# ME433Schematic.net
KiCad netlist of a schematic drawn in EAGLE
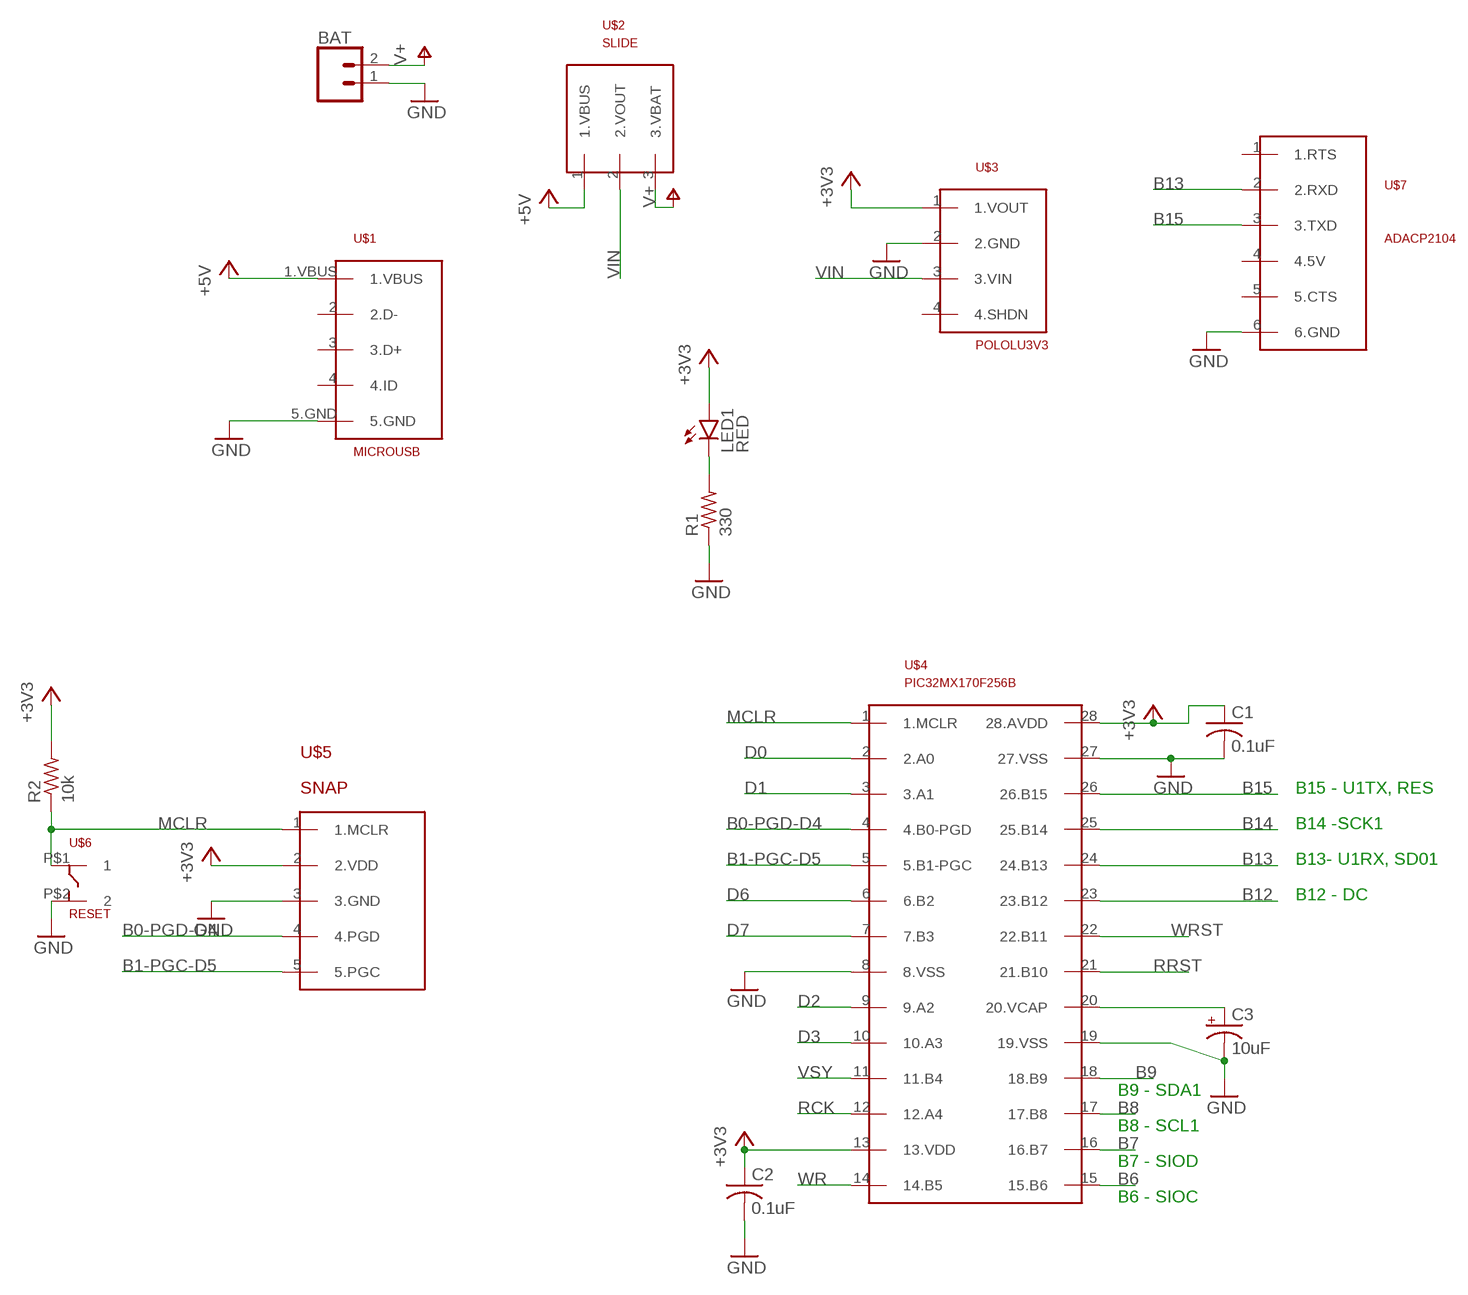
[diagram p0: schematic, sheet 1, part 1 of 2]
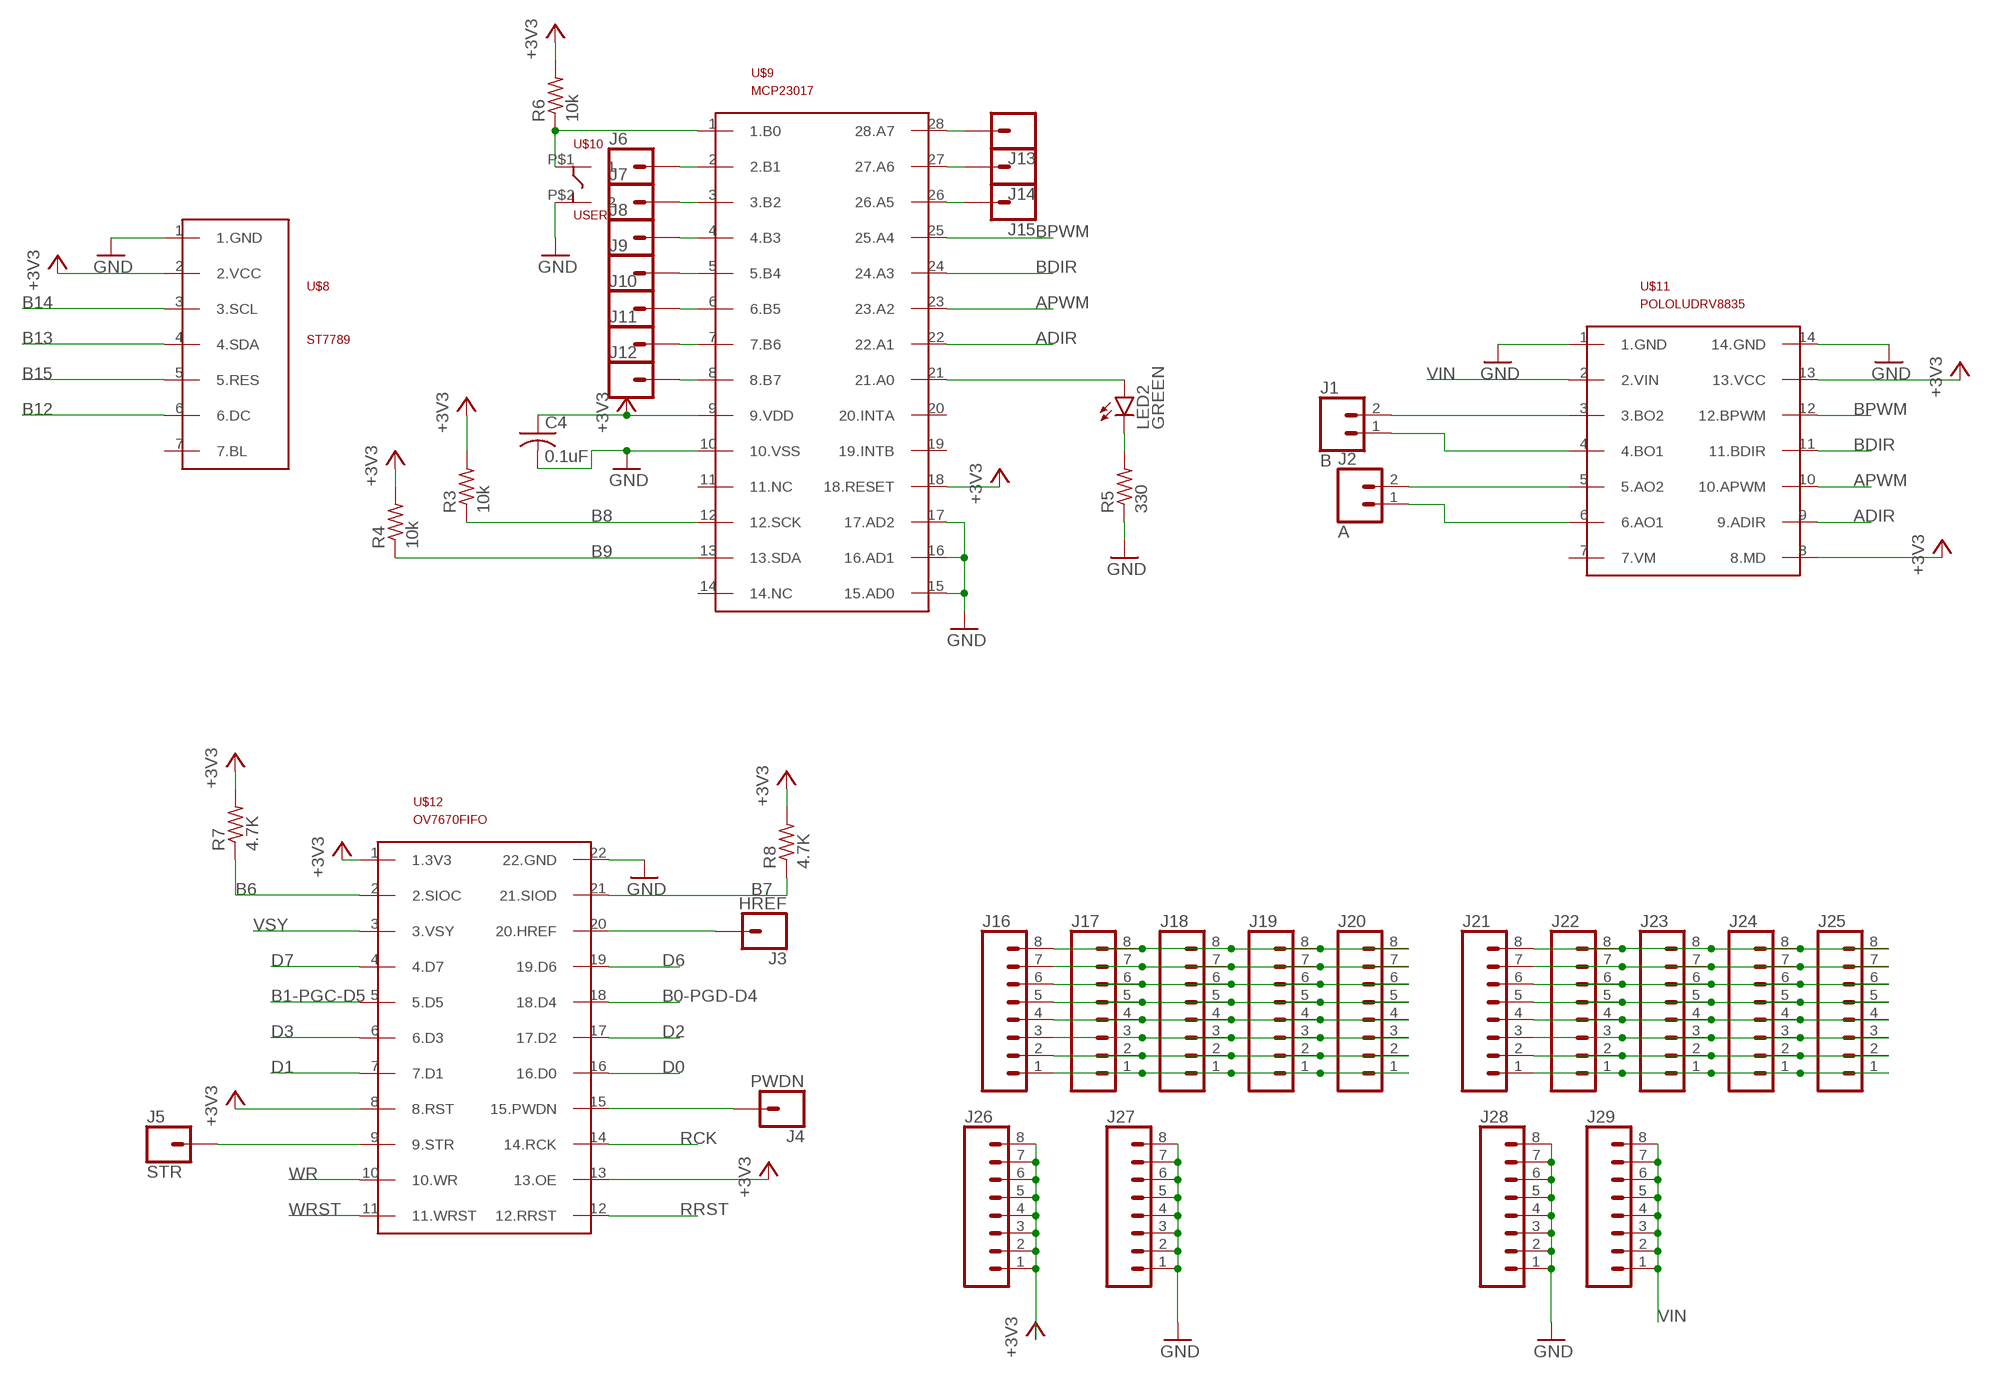
[diagram p1: schematic, sheet 1, part 2 of 2]

(export (version "E")
  (design (tool "Eeschema 10.0.6"))
  (components
    (comp (ref "BAT")
      (value "CONN_02")
      (footprint "eagle-import:1X02")
      (libsource (lib "eagle-import") (part "CONN_02"))
    )
    (comp (ref "C1")
      (value "0.1uF")
      (footprint "eagle-import:C025-030X050")
      (libsource (lib "eagle-import") (part "C-US025-030X050"))
    )
    (comp (ref "C2")
      (value "0.1uF")
      (footprint "eagle-import:C025-030X050")
      (libsource (lib "eagle-import") (part "C-US025-030X050"))
    )
    (comp (ref "C3")
      (value "10uF")
      (footprint "eagle-import:B45181B")
      (libsource (lib "eagle-import") (part "CPOL-USB45181B"))
    )
    (comp (ref "C4")
      (value "0.1uF")
      (footprint "eagle-import:C025-030X050")
      (libsource (lib "eagle-import") (part "C-US025-030X050"))
    )
    (comp (ref "J1")
      (value "B")
      (footprint "eagle-import:1X02")
      (libsource (lib "eagle-import") (part "CONN_02"))
    )
    (comp (ref "J2")
      (value "A")
      (footprint "eagle-import:1X02")
      (libsource (lib "eagle-import") (part "CONN_02"))
    )
    (comp (ref "J3")
      (value "HREF")
      (footprint "eagle-import:1X01")
      (libsource (lib "eagle-import") (part "CONN_01"))
    )
    (comp (ref "J4")
      (value "PWDN")
      (footprint "eagle-import:1X01")
      (libsource (lib "eagle-import") (part "CONN_01"))
    )
    (comp (ref "J5")
      (value "STR")
      (footprint "eagle-import:1X01")
      (libsource (lib "eagle-import") (part "CONN_01"))
    )
    (comp (ref "J6")
      (value "CONN_01")
      (footprint "eagle-import:1X01")
      (libsource (lib "eagle-import") (part "CONN_01"))
    )
    (comp (ref "J7")
      (value "CONN_01")
      (footprint "eagle-import:1X01")
      (libsource (lib "eagle-import") (part "CONN_01"))
    )
    (comp (ref "J8")
      (value "CONN_01")
      (footprint "eagle-import:1X01")
      (libsource (lib "eagle-import") (part "CONN_01"))
    )
    (comp (ref "J9")
      (value "CONN_01")
      (footprint "eagle-import:1X01")
      (libsource (lib "eagle-import") (part "CONN_01"))
    )
    (comp (ref "J10")
      (value "CONN_01")
      (footprint "eagle-import:1X01")
      (libsource (lib "eagle-import") (part "CONN_01"))
    )
    (comp (ref "J11")
      (value "CONN_01")
      (footprint "eagle-import:1X01")
      (libsource (lib "eagle-import") (part "CONN_01"))
    )
    (comp (ref "J12")
      (value "CONN_01")
      (footprint "eagle-import:1X01")
      (libsource (lib "eagle-import") (part "CONN_01"))
    )
    (comp (ref "J13")
      (value "CONN_01")
      (footprint "eagle-import:1X01")
      (libsource (lib "eagle-import") (part "CONN_01"))
    )
    (comp (ref "J14")
      (value "CONN_01")
      (footprint "eagle-import:1X01")
      (libsource (lib "eagle-import") (part "CONN_01"))
    )
    (comp (ref "J15")
      (value "CONN_01")
      (footprint "eagle-import:1X01")
      (libsource (lib "eagle-import") (part "CONN_01"))
    )
    (comp (ref "J16")
      (value "CONN_08\"")
      (footprint "eagle-import:1X08")
      (libsource (lib "eagle-import") (part "CONN_08{dblquote}"))
    )
    (comp (ref "J17")
      (value "CONN_08\"")
      (footprint "eagle-import:1X08")
      (libsource (lib "eagle-import") (part "CONN_08{dblquote}"))
    )
    (comp (ref "J18")
      (value "CONN_08\"")
      (footprint "eagle-import:1X08")
      (libsource (lib "eagle-import") (part "CONN_08{dblquote}"))
    )
    (comp (ref "J19")
      (value "CONN_08\"")
      (footprint "eagle-import:1X08")
      (libsource (lib "eagle-import") (part "CONN_08{dblquote}"))
    )
    (comp (ref "J20")
      (value "CONN_08\"")
      (footprint "eagle-import:1X08")
      (libsource (lib "eagle-import") (part "CONN_08{dblquote}"))
    )
    (comp (ref "J21")
      (value "CONN_08\"")
      (footprint "eagle-import:1X08")
      (libsource (lib "eagle-import") (part "CONN_08{dblquote}"))
    )
    (comp (ref "J22")
      (value "CONN_08\"")
      (footprint "eagle-import:1X08")
      (libsource (lib "eagle-import") (part "CONN_08{dblquote}"))
    )
    (comp (ref "J23")
      (value "CONN_08\"")
      (footprint "eagle-import:1X08")
      (libsource (lib "eagle-import") (part "CONN_08{dblquote}"))
    )
    (comp (ref "J24")
      (value "CONN_08\"")
      (footprint "eagle-import:1X08")
      (libsource (lib "eagle-import") (part "CONN_08{dblquote}"))
    )
    (comp (ref "J25")
      (value "CONN_08\"")
      (footprint "eagle-import:1X08")
      (libsource (lib "eagle-import") (part "CONN_08{dblquote}"))
    )
    (comp (ref "J26")
      (value "CONN_08\"")
      (footprint "eagle-import:1X08")
      (libsource (lib "eagle-import") (part "CONN_08{dblquote}"))
    )
    (comp (ref "J27")
      (value "CONN_08\"")
      (footprint "eagle-import:1X08")
      (libsource (lib "eagle-import") (part "CONN_08{dblquote}"))
    )
    (comp (ref "J28")
      (value "CONN_08\"")
      (footprint "eagle-import:1X08")
      (libsource (lib "eagle-import") (part "CONN_08{dblquote}"))
    )
    (comp (ref "J29")
      (value "CONN_08\"")
      (footprint "eagle-import:1X08")
      (libsource (lib "eagle-import") (part "CONN_08{dblquote}"))
    )
    (comp (ref "LED1")
      (value "RED")
      (footprint "eagle-import:LED3MM")
      (libsource (lib "eagle-import") (part "LED3MM"))
    )
    (comp (ref "LED2")
      (value "GREEN")
      (footprint "eagle-import:LED3MM")
      (libsource (lib "eagle-import") (part "LED3MM"))
    )
    (comp (ref "R1")
      (value "330")
      (footprint "eagle-import:0207_10")
      (libsource (lib "eagle-import") (part "R-US_0207/10"))
    )
    (comp (ref "R2")
      (value "10k")
      (footprint "eagle-import:0207_10")
      (libsource (lib "eagle-import") (part "R-US_0207/10"))
    )
    (comp (ref "R3")
      (value "10k")
      (footprint "eagle-import:0207_10")
      (libsource (lib "eagle-import") (part "R-US_0207/10"))
    )
    (comp (ref "R4")
      (value "10k")
      (footprint "eagle-import:0207_10")
      (libsource (lib "eagle-import") (part "R-US_0207/10"))
    )
    (comp (ref "R5")
      (value "330")
      (footprint "eagle-import:0207_10")
      (libsource (lib "eagle-import") (part "R-US_0207/10"))
    )
    (comp (ref "R6")
      (value "10k")
      (footprint "eagle-import:0207_10")
      (libsource (lib "eagle-import") (part "R-US_0207/10"))
    )
    (comp (ref "R7")
      (value "4.7K")
      (footprint "eagle-import:0207_10")
      (libsource (lib "eagle-import") (part "R-US_0207/10"))
    )
    (comp (ref "R8")
      (value "4.7K")
      (footprint "eagle-import:0207_10")
      (libsource (lib "eagle-import") (part "R-US_0207/10"))
    )
    (comp (ref "U$1")
      (value "MICROUSB")
      (footprint "eagle-import:MICROUSB")
      (libsource (lib "eagle-import") (part "MICROUSB"))
    )
    (comp (ref "U$2")
      (value "SLIDE")
      (footprint "eagle-import:SLIDE")
      (libsource (lib "eagle-import") (part "SLIDE"))
    )
    (comp (ref "U$3")
      (value "POLOLU3V3")
      (footprint "eagle-import:POLOLU3V3")
      (libsource (lib "eagle-import") (part "POLOLU3V3"))
    )
    (comp (ref "U$4")
      (value "PIC32MX170F256B")
      (footprint "eagle-import:DIL28-3")
      (libsource (lib "eagle-import") (part "PIC32MX170F256B"))
    )
    (comp (ref "U$5")
      (value "SNAP")
      (footprint "eagle-import:SNAP")
      (libsource (lib "eagle-import") (part "SNAP"))
    )
    (comp (ref "U$6")
      (value "RESET")
      (footprint "eagle-import:PUSH")
      (libsource (lib "eagle-import") (part "PUSH"))
    )
    (comp (ref "U$7")
      (value "ADACP2104")
      (footprint "eagle-import:ADACP2104")
      (libsource (lib "eagle-import") (part "ADACP2104"))
    )
    (comp (ref "U$8")
      (value "ST7789")
      (footprint "eagle-import:ST7789")
      (libsource (lib "eagle-import") (part "ST7789"))
    )
    (comp (ref "U$9")
      (value "MCP23017")
      (footprint "eagle-import:DIL28-3")
      (libsource (lib "eagle-import") (part "MCP23017"))
    )
    (comp (ref "U$10")
      (value "USER")
      (footprint "eagle-import:PUSH")
      (libsource (lib "eagle-import") (part "PUSH"))
    )
    (comp (ref "U$11")
      (value "POLOLUDRV8835")
      (footprint "eagle-import:POLOLUDRV8835")
      (libsource (lib "eagle-import") (part "POLOLUDRV8835"))
    )
    (comp (ref "U$12")
      (value "OV7670FIFO")
      (footprint "eagle-import:OV7670FIFO")
      (libsource (lib "eagle-import") (part "OV7670FIFO"))
    )
  )
  (nets
    (net (code "1") (name "+3V3") (class "Default")
      (node (ref "C1") (pin "1") (pinfunction "1_1") (pintype "passive"))
      (node (ref "C2") (pin "1") (pinfunction "1_1") (pintype "passive"))
      (node (ref "C4") (pin "1") (pinfunction "1_1") (pintype "passive"))
      (node (ref "J26") (pin "1") (pinfunction "1_1") (pintype "passive"))
      (node (ref "J26") (pin "2") (pinfunction "2_2") (pintype "passive"))
      (node (ref "J26") (pin "3") (pinfunction "3_3") (pintype "passive"))
      (node (ref "J26") (pin "4") (pinfunction "4_4") (pintype "passive"))
      (node (ref "J26") (pin "5") (pinfunction "5_5") (pintype "passive"))
      (node (ref "J26") (pin "6") (pinfunction "6_6") (pintype "passive"))
      (node (ref "J26") (pin "7") (pinfunction "7_7") (pintype "passive"))
      (node (ref "J26") (pin "8") (pinfunction "8_8") (pintype "passive"))
      (node (ref "LED1") (pin "A") (pinfunction "A_A") (pintype "passive"))
      (node (ref "R2") (pin "2") (pinfunction "2_2") (pintype "passive"))
      (node (ref "R3") (pin "2") (pinfunction "2_2") (pintype "passive"))
      (node (ref "R4") (pin "2") (pinfunction "2_2") (pintype "passive"))
      (node (ref "R6") (pin "2") (pinfunction "2_2") (pintype "passive"))
      (node (ref "R7") (pin "2") (pinfunction "2_2") (pintype "passive"))
      (node (ref "R8") (pin "2") (pinfunction "2_2") (pintype "passive"))
      (node (ref "U$11") (pin "13") (pinfunction "13.VCC_13") (pintype "bidirectional"))
      (node (ref "U$11") (pin "8") (pinfunction "8.MD_8") (pintype "bidirectional"))
      (node (ref "U$12") (pin "1") (pinfunction "1.3V3_1") (pintype "bidirectional"))
      (node (ref "U$12") (pin "13") (pinfunction "13.OE_13") (pintype "bidirectional"))
      (node (ref "U$12") (pin "8") (pinfunction "8.RST_8") (pintype "bidirectional"))
      (node (ref "U$3") (pin "1") (pinfunction "1.VOUT_1") (pintype "bidirectional"))
      (node (ref "U$4") (pin "13") (pinfunction "13.VDD_13") (pintype "bidirectional"))
      (node (ref "U$4") (pin "28") (pinfunction "28.AVDD_28") (pintype "bidirectional"))
      (node (ref "U$5") (pin "2") (pinfunction "2.VDD_2") (pintype "bidirectional"))
      (node (ref "U$8") (pin "2") (pinfunction "2.VCC_2") (pintype "bidirectional"))
      (node (ref "U$9") (pin "18") (pinfunction "18.RESET_18") (pintype "bidirectional"))
      (node (ref "U$9") (pin "9") (pinfunction "9.VDD_9") (pintype "bidirectional"))
    )
    (net (code "2") (name "+5V") (class "Default")
      (node (ref "U$1") (pin "1.VBUS") (pinfunction "1.VBUS_1.VBUS") (pintype "bidirectional"))
      (node (ref "U$2") (pin "1") (pinfunction "1.VBUS_1") (pintype "bidirectional"))
    )
    (net (code "3") (name "/ADIR") (class "Default")
      (node (ref "U$11") (pin "9") (pinfunction "9.ADIR_9") (pintype "bidirectional"))
      (node (ref "U$9") (pin "22") (pinfunction "22.A1_22") (pintype "bidirectional"))
    )
    (net (code "4") (name "/APWM") (class "Default")
      (node (ref "U$11") (pin "10") (pinfunction "10.APWM_10") (pintype "bidirectional"))
      (node (ref "U$9") (pin "23") (pinfunction "23.A2_23") (pintype "bidirectional"))
    )
    (net (code "5") (name "/B0-PGD-D4") (class "Default")
      (node (ref "U$12") (pin "18") (pinfunction "18.D4_18") (pintype "bidirectional"))
      (node (ref "U$4") (pin "4") (pinfunction "4.B0-PGD_4") (pintype "bidirectional"))
      (node (ref "U$5") (pin "4") (pinfunction "4.PGD_4") (pintype "bidirectional"))
    )
    (net (code "6") (name "/B1-PGC-D5") (class "Default")
      (node (ref "U$12") (pin "5") (pinfunction "5.D5_5") (pintype "bidirectional"))
      (node (ref "U$4") (pin "5") (pinfunction "5.B1-PGC_5") (pintype "bidirectional"))
      (node (ref "U$5") (pin "5") (pinfunction "5.PGC_5") (pintype "bidirectional"))
    )
    (net (code "7") (name "/B6") (class "Default")
      (node (ref "R7") (pin "1") (pinfunction "1_1") (pintype "passive"))
      (node (ref "U$12") (pin "2") (pinfunction "2.SIOC_2") (pintype "bidirectional"))
      (node (ref "U$4") (pin "15") (pinfunction "15.B6_15") (pintype "bidirectional"))
    )
    (net (code "8") (name "/B7") (class "Default")
      (node (ref "R8") (pin "1") (pinfunction "1_1") (pintype "passive"))
      (node (ref "U$12") (pin "21") (pinfunction "21.SIOD_21") (pintype "bidirectional"))
      (node (ref "U$4") (pin "16") (pinfunction "16.B7_16") (pintype "bidirectional"))
    )
    (net (code "9") (name "/B8") (class "Default")
      (node (ref "R3") (pin "1") (pinfunction "1_1") (pintype "passive"))
      (node (ref "U$4") (pin "17") (pinfunction "17.B8_17") (pintype "bidirectional"))
      (node (ref "U$9") (pin "12") (pinfunction "12.SCK_12") (pintype "bidirectional"))
    )
    (net (code "10") (name "/B9") (class "Default")
      (node (ref "R4") (pin "1") (pinfunction "1_1") (pintype "passive"))
      (node (ref "U$4") (pin "18") (pinfunction "18.B9_18") (pintype "bidirectional"))
      (node (ref "U$9") (pin "13") (pinfunction "13.SDA_13") (pintype "bidirectional"))
    )
    (net (code "11") (name "/B12") (class "Default")
      (node (ref "U$4") (pin "23") (pinfunction "23.B12_23") (pintype "bidirectional"))
      (node (ref "U$8") (pin "6") (pinfunction "6.DC_6") (pintype "bidirectional"))
    )
    (net (code "12") (name "/B13") (class "Default")
      (node (ref "U$4") (pin "24") (pinfunction "24.B13_24") (pintype "bidirectional"))
      (node (ref "U$7") (pin "2") (pinfunction "2.RXD_2") (pintype "bidirectional"))
      (node (ref "U$8") (pin "4") (pinfunction "4.SDA_4") (pintype "bidirectional"))
    )
    (net (code "13") (name "/B14") (class "Default")
      (node (ref "U$4") (pin "25") (pinfunction "25.B14_25") (pintype "bidirectional"))
      (node (ref "U$8") (pin "3") (pinfunction "3.SCL_3") (pintype "bidirectional"))
    )
    (net (code "14") (name "/B15") (class "Default")
      (node (ref "U$4") (pin "26") (pinfunction "26.B15_26") (pintype "bidirectional"))
      (node (ref "U$7") (pin "3") (pinfunction "3.TXD_3") (pintype "bidirectional"))
      (node (ref "U$8") (pin "5") (pinfunction "5.RES_5") (pintype "bidirectional"))
    )
    (net (code "15") (name "/BDIR") (class "Default")
      (node (ref "U$11") (pin "11") (pinfunction "11.BDIR_11") (pintype "bidirectional"))
      (node (ref "U$9") (pin "24") (pinfunction "24.A3_24") (pintype "bidirectional"))
    )
    (net (code "16") (name "/BPWM") (class "Default")
      (node (ref "U$11") (pin "12") (pinfunction "12.BPWM_12") (pintype "bidirectional"))
      (node (ref "U$9") (pin "25") (pinfunction "25.A4_25") (pintype "bidirectional"))
    )
    (net (code "17") (name "/D0") (class "Default")
      (node (ref "U$12") (pin "16") (pinfunction "16.D0_16") (pintype "bidirectional"))
      (node (ref "U$4") (pin "2") (pinfunction "2.A0_2") (pintype "bidirectional"))
    )
    (net (code "18") (name "/D1") (class "Default")
      (node (ref "U$12") (pin "7") (pinfunction "7.D1_7") (pintype "bidirectional"))
      (node (ref "U$4") (pin "3") (pinfunction "3.A1_3") (pintype "bidirectional"))
    )
    (net (code "19") (name "/D2") (class "Default")
      (node (ref "U$12") (pin "17") (pinfunction "17.D2_17") (pintype "bidirectional"))
      (node (ref "U$4") (pin "9") (pinfunction "9.A2_9") (pintype "bidirectional"))
    )
    (net (code "20") (name "/D3") (class "Default")
      (node (ref "U$12") (pin "6") (pinfunction "6.D3_6") (pintype "bidirectional"))
      (node (ref "U$4") (pin "10") (pinfunction "10.A3_10") (pintype "bidirectional"))
    )
    (net (code "21") (name "/D6") (class "Default")
      (node (ref "U$12") (pin "19") (pinfunction "19.D6_19") (pintype "bidirectional"))
      (node (ref "U$4") (pin "6") (pinfunction "6.B2_6") (pintype "bidirectional"))
    )
    (net (code "22") (name "/D7") (class "Default")
      (node (ref "U$12") (pin "4") (pinfunction "4.D7_4") (pintype "bidirectional"))
      (node (ref "U$4") (pin "7") (pinfunction "7.B3_7") (pintype "bidirectional"))
    )
    (net (code "23") (name "/MCLR") (class "Default")
      (node (ref "R2") (pin "1") (pinfunction "1_1") (pintype "passive"))
      (node (ref "U$4") (pin "1") (pinfunction "1.MCLR_1") (pintype "bidirectional"))
      (node (ref "U$5") (pin "1") (pinfunction "1.MCLR_1") (pintype "bidirectional"))
      (node (ref "U$6") (pin "P$1") (pinfunction "1_P$1") (pintype "bidirectional"))
    )
    (net (code "24") (name "/RCK") (class "Default")
      (node (ref "U$12") (pin "14") (pinfunction "14.RCK_14") (pintype "bidirectional"))
      (node (ref "U$4") (pin "12") (pinfunction "12.A4_12") (pintype "bidirectional"))
    )
    (net (code "25") (name "/RRST") (class "Default")
      (node (ref "U$12") (pin "12") (pinfunction "12.RRST_12") (pintype "bidirectional"))
      (node (ref "U$4") (pin "21") (pinfunction "21.B10_21") (pintype "bidirectional"))
    )
    (net (code "26") (name "/VIN") (class "Default")
      (node (ref "J29") (pin "1") (pinfunction "1_1") (pintype "passive"))
      (node (ref "J29") (pin "2") (pinfunction "2_2") (pintype "passive"))
      (node (ref "J29") (pin "3") (pinfunction "3_3") (pintype "passive"))
      (node (ref "J29") (pin "4") (pinfunction "4_4") (pintype "passive"))
      (node (ref "J29") (pin "5") (pinfunction "5_5") (pintype "passive"))
      (node (ref "J29") (pin "6") (pinfunction "6_6") (pintype "passive"))
      (node (ref "J29") (pin "7") (pinfunction "7_7") (pintype "passive"))
      (node (ref "J29") (pin "8") (pinfunction "8_8") (pintype "passive"))
      (node (ref "U$11") (pin "2") (pinfunction "2.VIN_2") (pintype "bidirectional"))
      (node (ref "U$2") (pin "2") (pinfunction "2.VOUT_2") (pintype "bidirectional"))
      (node (ref "U$3") (pin "3") (pinfunction "3.VIN_3") (pintype "bidirectional"))
    )
    (net (code "27") (name "/VSY") (class "Default")
      (node (ref "U$12") (pin "3") (pinfunction "3.VSY_3") (pintype "bidirectional"))
      (node (ref "U$4") (pin "11") (pinfunction "11.B4_11") (pintype "bidirectional"))
    )
    (net (code "28") (name "/WR") (class "Default")
      (node (ref "U$12") (pin "10") (pinfunction "10.WR_10") (pintype "bidirectional"))
      (node (ref "U$4") (pin "14") (pinfunction "14.B5_14") (pintype "bidirectional"))
    )
    (net (code "29") (name "/WRST") (class "Default")
      (node (ref "U$12") (pin "11") (pinfunction "11.WRST_11") (pintype "bidirectional"))
      (node (ref "U$4") (pin "22") (pinfunction "22.B11_22") (pintype "bidirectional"))
    )
    (net (code "30") (name "GND") (class "Default")
      (node (ref "BAT") (pin "1") (pinfunction "1_1") (pintype "passive"))
      (node (ref "C1") (pin "2") (pinfunction "2_2") (pintype "passive"))
      (node (ref "C2") (pin "2") (pinfunction "2_2") (pintype "passive"))
      (node (ref "C3") (pin "-") (pinfunction "-_-") (pintype "passive"))
      (node (ref "C4") (pin "2") (pinfunction "2_2") (pintype "passive"))
      (node (ref "J27") (pin "1") (pinfunction "1_1") (pintype "passive"))
      (node (ref "J27") (pin "2") (pinfunction "2_2") (pintype "passive"))
      (node (ref "J27") (pin "3") (pinfunction "3_3") (pintype "passive"))
      (node (ref "J27") (pin "4") (pinfunction "4_4") (pintype "passive"))
      (node (ref "J27") (pin "5") (pinfunction "5_5") (pintype "passive"))
      (node (ref "J27") (pin "6") (pinfunction "6_6") (pintype "passive"))
      (node (ref "J27") (pin "7") (pinfunction "7_7") (pintype "passive"))
      (node (ref "J27") (pin "8") (pinfunction "8_8") (pintype "passive"))
      (node (ref "J28") (pin "1") (pinfunction "1_1") (pintype "passive"))
      (node (ref "J28") (pin "2") (pinfunction "2_2") (pintype "passive"))
      (node (ref "J28") (pin "3") (pinfunction "3_3") (pintype "passive"))
      (node (ref "J28") (pin "4") (pinfunction "4_4") (pintype "passive"))
      (node (ref "J28") (pin "5") (pinfunction "5_5") (pintype "passive"))
      (node (ref "J28") (pin "6") (pinfunction "6_6") (pintype "passive"))
      (node (ref "J28") (pin "7") (pinfunction "7_7") (pintype "passive"))
      (node (ref "J28") (pin "8") (pinfunction "8_8") (pintype "passive"))
      (node (ref "R1") (pin "1") (pinfunction "1_1") (pintype "passive"))
      (node (ref "R5") (pin "1") (pinfunction "1_1") (pintype "passive"))
      (node (ref "U$1") (pin "5.GND") (pinfunction "5.GND_5.GND") (pintype "bidirectional"))
      (node (ref "U$10") (pin "P$2") (pinfunction "2_P$2") (pintype "bidirectional"))
      (node (ref "U$11") (pin "1") (pinfunction "1.GND_1") (pintype "bidirectional"))
      (node (ref "U$11") (pin "14") (pinfunction "14.GND_14") (pintype "bidirectional"))
      (node (ref "U$12") (pin "22") (pinfunction "22.GND_22") (pintype "bidirectional"))
      (node (ref "U$3") (pin "2") (pinfunction "2.GND_2") (pintype "bidirectional"))
      (node (ref "U$4") (pin "19") (pinfunction "19.VSS_19") (pintype "bidirectional"))
      (node (ref "U$4") (pin "27") (pinfunction "27.VSS_27") (pintype "bidirectional"))
      (node (ref "U$4") (pin "8") (pinfunction "8.VSS_8") (pintype "bidirectional"))
      (node (ref "U$5") (pin "3") (pinfunction "3.GND_3") (pintype "bidirectional"))
      (node (ref "U$6") (pin "P$2") (pinfunction "2_P$2") (pintype "bidirectional"))
      (node (ref "U$7") (pin "6") (pinfunction "6.GND_6") (pintype "bidirectional"))
      (node (ref "U$8") (pin "1") (pinfunction "1.GND_1") (pintype "bidirectional"))
      (node (ref "U$9") (pin "10") (pinfunction "10.VSS_10") (pintype "bidirectional"))
      (node (ref "U$9") (pin "15") (pinfunction "15.AD0_15") (pintype "bidirectional"))
      (node (ref "U$9") (pin "16") (pinfunction "16.AD1_16") (pintype "bidirectional"))
      (node (ref "U$9") (pin "17") (pinfunction "17.AD2_17") (pintype "bidirectional"))
    )
    (net (code "31") (name "Net-(J16-Pad1)") (class "Default")
      (node (ref "J16") (pin "1") (pinfunction "1_1") (pintype "passive"))
      (node (ref "J17") (pin "1") (pinfunction "1_1") (pintype "passive"))
      (node (ref "J18") (pin "1") (pinfunction "1_1") (pintype "passive"))
      (node (ref "J19") (pin "1") (pinfunction "1_1") (pintype "passive"))
      (node (ref "J20") (pin "1") (pinfunction "1_1") (pintype "passive"))
    )
    (net (code "32") (name "Net-(J16-Pad2)") (class "Default")
      (node (ref "J16") (pin "2") (pinfunction "2_2") (pintype "passive"))
      (node (ref "J17") (pin "2") (pinfunction "2_2") (pintype "passive"))
      (node (ref "J18") (pin "2") (pinfunction "2_2") (pintype "passive"))
      (node (ref "J19") (pin "2") (pinfunction "2_2") (pintype "passive"))
      (node (ref "J20") (pin "2") (pinfunction "2_2") (pintype "passive"))
    )
    (net (code "33") (name "Net-(J16-Pad3)") (class "Default")
      (node (ref "J16") (pin "3") (pinfunction "3_3") (pintype "passive"))
      (node (ref "J17") (pin "3") (pinfunction "3_3") (pintype "passive"))
      (node (ref "J18") (pin "3") (pinfunction "3_3") (pintype "passive"))
      (node (ref "J19") (pin "3") (pinfunction "3_3") (pintype "passive"))
      (node (ref "J20") (pin "3") (pinfunction "3_3") (pintype "passive"))
    )
    (net (code "34") (name "Net-(J16-Pad4)") (class "Default")
      (node (ref "J16") (pin "4") (pinfunction "4_4") (pintype "passive"))
      (node (ref "J17") (pin "4") (pinfunction "4_4") (pintype "passive"))
      (node (ref "J18") (pin "4") (pinfunction "4_4") (pintype "passive"))
      (node (ref "J19") (pin "4") (pinfunction "4_4") (pintype "passive"))
      (node (ref "J20") (pin "4") (pinfunction "4_4") (pintype "passive"))
    )
    (net (code "35") (name "Net-(J16-Pad5)") (class "Default")
      (node (ref "J16") (pin "5") (pinfunction "5_5") (pintype "passive"))
      (node (ref "J17") (pin "5") (pinfunction "5_5") (pintype "passive"))
      (node (ref "J18") (pin "5") (pinfunction "5_5") (pintype "passive"))
      (node (ref "J19") (pin "5") (pinfunction "5_5") (pintype "passive"))
      (node (ref "J20") (pin "5") (pinfunction "5_5") (pintype "passive"))
    )
    (net (code "36") (name "Net-(J16-Pad6)") (class "Default")
      (node (ref "J16") (pin "6") (pinfunction "6_6") (pintype "passive"))
      (node (ref "J17") (pin "6") (pinfunction "6_6") (pintype "passive"))
      (node (ref "J18") (pin "6") (pinfunction "6_6") (pintype "passive"))
      (node (ref "J19") (pin "6") (pinfunction "6_6") (pintype "passive"))
      (node (ref "J20") (pin "6") (pinfunction "6_6") (pintype "passive"))
    )
    (net (code "37") (name "Net-(J16-Pad7)") (class "Default")
      (node (ref "J16") (pin "7") (pinfunction "7_7") (pintype "passive"))
      (node (ref "J17") (pin "7") (pinfunction "7_7") (pintype "passive"))
      (node (ref "J18") (pin "7") (pinfunction "7_7") (pintype "passive"))
      (node (ref "J19") (pin "7") (pinfunction "7_7") (pintype "passive"))
      (node (ref "J20") (pin "7") (pinfunction "7_7") (pintype "passive"))
    )
    (net (code "38") (name "Net-(J16-Pad8)") (class "Default")
      (node (ref "J16") (pin "8") (pinfunction "8_8") (pintype "passive"))
      (node (ref "J17") (pin "8") (pinfunction "8_8") (pintype "passive"))
      (node (ref "J18") (pin "8") (pinfunction "8_8") (pintype "passive"))
      (node (ref "J19") (pin "8") (pinfunction "8_8") (pintype "passive"))
      (node (ref "J20") (pin "8") (pinfunction "8_8") (pintype "passive"))
    )
    (net (code "39") (name "Net-(J21-Pad1)") (class "Default")
      (node (ref "J21") (pin "1") (pinfunction "1_1") (pintype "passive"))
      (node (ref "J22") (pin "1") (pinfunction "1_1") (pintype "passive"))
      (node (ref "J23") (pin "1") (pinfunction "1_1") (pintype "passive"))
      (node (ref "J24") (pin "1") (pinfunction "1_1") (pintype "passive"))
      (node (ref "J25") (pin "1") (pinfunction "1_1") (pintype "passive"))
    )
    (net (code "40") (name "Net-(J21-Pad2)") (class "Default")
      (node (ref "J21") (pin "2") (pinfunction "2_2") (pintype "passive"))
      (node (ref "J22") (pin "2") (pinfunction "2_2") (pintype "passive"))
      (node (ref "J23") (pin "2") (pinfunction "2_2") (pintype "passive"))
      (node (ref "J24") (pin "2") (pinfunction "2_2") (pintype "passive"))
      (node (ref "J25") (pin "2") (pinfunction "2_2") (pintype "passive"))
    )
    (net (code "41") (name "Net-(J21-Pad3)") (class "Default")
      (node (ref "J21") (pin "3") (pinfunction "3_3") (pintype "passive"))
      (node (ref "J22") (pin "3") (pinfunction "3_3") (pintype "passive"))
      (node (ref "J23") (pin "3") (pinfunction "3_3") (pintype "passive"))
      (node (ref "J24") (pin "3") (pinfunction "3_3") (pintype "passive"))
      (node (ref "J25") (pin "3") (pinfunction "3_3") (pintype "passive"))
    )
    (net (code "42") (name "Net-(J21-Pad4)") (class "Default")
      (node (ref "J21") (pin "4") (pinfunction "4_4") (pintype "passive"))
      (node (ref "J22") (pin "4") (pinfunction "4_4") (pintype "passive"))
      (node (ref "J23") (pin "4") (pinfunction "4_4") (pintype "passive"))
      (node (ref "J24") (pin "4") (pinfunction "4_4") (pintype "passive"))
      (node (ref "J25") (pin "4") (pinfunction "4_4") (pintype "passive"))
    )
    (net (code "43") (name "Net-(J21-Pad5)") (class "Default")
      (node (ref "J21") (pin "5") (pinfunction "5_5") (pintype "passive"))
      (node (ref "J22") (pin "5") (pinfunction "5_5") (pintype "passive"))
      (node (ref "J23") (pin "5") (pinfunction "5_5") (pintype "passive"))
      (node (ref "J24") (pin "5") (pinfunction "5_5") (pintype "passive"))
      (node (ref "J25") (pin "5") (pinfunction "5_5") (pintype "passive"))
    )
    (net (code "44") (name "Net-(J21-Pad6)") (class "Default")
      (node (ref "J21") (pin "6") (pinfunction "6_6") (pintype "passive"))
      (node (ref "J22") (pin "6") (pinfunction "6_6") (pintype "passive"))
      (node (ref "J23") (pin "6") (pinfunction "6_6") (pintype "passive"))
      (node (ref "J24") (pin "6") (pinfunction "6_6") (pintype "passive"))
      (node (ref "J25") (pin "6") (pinfunction "6_6") (pintype "passive"))
    )
    (net (code "45") (name "Net-(J21-Pad7)") (class "Default")
      (node (ref "J21") (pin "7") (pinfunction "7_7") (pintype "passive"))
      (node (ref "J22") (pin "7") (pinfunction "7_7") (pintype "passive"))
      (node (ref "J23") (pin "7") (pinfunction "7_7") (pintype "passive"))
      (node (ref "J24") (pin "7") (pinfunction "7_7") (pintype "passive"))
      (node (ref "J25") (pin "7") (pinfunction "7_7") (pintype "passive"))
    )
    (net (code "46") (name "Net-(J21-Pad8)") (class "Default")
      (node (ref "J21") (pin "8") (pinfunction "8_8") (pintype "passive"))
      (node (ref "J22") (pin "8") (pinfunction "8_8") (pintype "passive"))
      (node (ref "J23") (pin "8") (pinfunction "8_8") (pintype "passive"))
      (node (ref "J24") (pin "8") (pinfunction "8_8") (pintype "passive"))
      (node (ref "J25") (pin "8") (pinfunction "8_8") (pintype "passive"))
    )
    (net (code "47") (name "Net-(LED1-C)") (class "Default")
      (node (ref "LED1") (pin "K") (pinfunction "C_K") (pintype "passive"))
      (node (ref "R1") (pin "2") (pinfunction "2_2") (pintype "passive"))
    )
    (net (code "48") (name "Net-(LED2-C)") (class "Default")
      (node (ref "LED2") (pin "K") (pinfunction "C_K") (pintype "passive"))
      (node (ref "R5") (pin "2") (pinfunction "2_2") (pintype "passive"))
    )
    (net (code "49") (name "Net-(U$4-20.VCAP)") (class "Default")
      (node (ref "C3") (pin "+") (pinfunction "+_+") (pintype "passive"))
      (node (ref "U$4") (pin "20") (pinfunction "20.VCAP_20") (pintype "bidirectional"))
    )
    (net (code "50") (name "Net-(U$9-2.B1)") (class "Default")
      (node (ref "J6") (pin "1") (pinfunction "1_1") (pintype "passive"))
      (node (ref "U$9") (pin "2") (pinfunction "2.B1_2") (pintype "bidirectional"))
    )
    (net (code "51") (name "Net-(U$9-3.B2)") (class "Default")
      (node (ref "J7") (pin "1") (pinfunction "1_1") (pintype "passive"))
      (node (ref "U$9") (pin "3") (pinfunction "3.B2_3") (pintype "bidirectional"))
    )
    (net (code "52") (name "Net-(U$9-4.B3)") (class "Default")
      (node (ref "J8") (pin "1") (pinfunction "1_1") (pintype "passive"))
      (node (ref "U$9") (pin "4") (pinfunction "4.B3_4") (pintype "bidirectional"))
    )
    (net (code "53") (name "Net-(U$9-5.B4)") (class "Default")
      (node (ref "J9") (pin "1") (pinfunction "1_1") (pintype "passive"))
      (node (ref "U$9") (pin "5") (pinfunction "5.B4_5") (pintype "bidirectional"))
    )
    (net (code "54") (name "Net-(U$9-6.B5)") (class "Default")
      (node (ref "J10") (pin "1") (pinfunction "1_1") (pintype "passive"))
      (node (ref "U$9") (pin "6") (pinfunction "6.B5_6") (pintype "bidirectional"))
    )
    (net (code "55") (name "Net-(U$9-7.B6)") (class "Default")
      (node (ref "J11") (pin "1") (pinfunction "1_1") (pintype "passive"))
      (node (ref "U$9") (pin "7") (pinfunction "7.B6_7") (pintype "bidirectional"))
    )
    (net (code "56") (name "Net-(U$9-8.B7)") (class "Default")
      (node (ref "J12") (pin "1") (pinfunction "1_1") (pintype "passive"))
      (node (ref "U$9") (pin "8") (pinfunction "8.B7_8") (pintype "bidirectional"))
    )
    (net (code "57") (name "Net-(U$9-21.A0)") (class "Default")
      (node (ref "LED2") (pin "A") (pinfunction "A_A") (pintype "passive"))
      (node (ref "U$9") (pin "21") (pinfunction "21.A0_21") (pintype "bidirectional"))
    )
    (net (code "58") (name "Net-(U$9-26.A5)") (class "Default")
      (node (ref "J15") (pin "1") (pinfunction "1_1") (pintype "passive"))
      (node (ref "U$9") (pin "26") (pinfunction "26.A5_26") (pintype "bidirectional"))
    )
    (net (code "59") (name "Net-(U$9-27.A6)") (class "Default")
      (node (ref "J14") (pin "1") (pinfunction "1_1") (pintype "passive"))
      (node (ref "U$9") (pin "27") (pinfunction "27.A6_27") (pintype "bidirectional"))
    )
    (net (code "60") (name "Net-(U$9-28.A7)") (class "Default")
      (node (ref "J13") (pin "1") (pinfunction "1_1") (pintype "passive"))
      (node (ref "U$9") (pin "28") (pinfunction "28.A7_28") (pintype "bidirectional"))
    )
    (net (code "61") (name "Net-(U$10-1)") (class "Default")
      (node (ref "R6") (pin "1") (pinfunction "1_1") (pintype "passive"))
      (node (ref "U$10") (pin "P$1") (pinfunction "1_P$1") (pintype "bidirectional"))
      (node (ref "U$9") (pin "1") (pinfunction "1.B0_1") (pintype "bidirectional"))
    )
    (net (code "62") (name "Net-(U$11-3.BO2)") (class "Default")
      (node (ref "J1") (pin "2") (pinfunction "2_2") (pintype "passive"))
      (node (ref "U$11") (pin "3") (pinfunction "3.BO2_3") (pintype "bidirectional"))
    )
    (net (code "63") (name "Net-(U$11-4.BO1)") (class "Default")
      (node (ref "J1") (pin "1") (pinfunction "1_1") (pintype "passive"))
      (node (ref "U$11") (pin "4") (pinfunction "4.BO1_4") (pintype "bidirectional"))
    )
    (net (code "64") (name "Net-(U$11-5.AO2)") (class "Default")
      (node (ref "J2") (pin "2") (pinfunction "2_2") (pintype "passive"))
      (node (ref "U$11") (pin "5") (pinfunction "5.AO2_5") (pintype "bidirectional"))
    )
    (net (code "65") (name "Net-(U$11-6.AO1)") (class "Default")
      (node (ref "J2") (pin "1") (pinfunction "1_1") (pintype "passive"))
      (node (ref "U$11") (pin "6") (pinfunction "6.AO1_6") (pintype "bidirectional"))
    )
    (net (code "66") (name "Net-(U$12-9.STR)") (class "Default")
      (node (ref "J5") (pin "1") (pinfunction "1_1") (pintype "passive"))
      (node (ref "U$12") (pin "9") (pinfunction "9.STR_9") (pintype "bidirectional"))
    )
    (net (code "67") (name "Net-(U$12-15.PWDN)") (class "Default")
      (node (ref "J4") (pin "1") (pinfunction "1_1") (pintype "passive"))
      (node (ref "U$12") (pin "15") (pinfunction "15.PWDN_15") (pintype "bidirectional"))
    )
    (net (code "68") (name "Net-(U$12-20.HREF)") (class "Default")
      (node (ref "J3") (pin "1") (pinfunction "1_1") (pintype "passive"))
      (node (ref "U$12") (pin "20") (pinfunction "20.HREF_20") (pintype "bidirectional"))
    )
    (net (code "69") (name "V+") (class "Default")
      (node (ref "BAT") (pin "2") (pinfunction "2_2") (pintype "passive"))
      (node (ref "U$2") (pin "3") (pinfunction "3.VBAT_3") (pintype "bidirectional"))
    )
    (net (code "70") (name "unconnected-(U$1-2.D--Pad2)") (class "Default")
      (node (ref "U$1") (pin "2") (pinfunction "2.D-_2") (pintype "bidirectional"))
    )
    (net (code "71") (name "unconnected-(U$1-3.D+-Pad3)") (class "Default")
      (node (ref "U$1") (pin "3") (pinfunction "3.D+_3") (pintype "bidirectional"))
    )
    (net (code "72") (name "unconnected-(U$1-4.ID-Pad4)") (class "Default")
      (node (ref "U$1") (pin "4") (pinfunction "4.ID_4") (pintype "bidirectional"))
    )
    (net (code "73") (name "unconnected-(U$3-4.SHDN-Pad4)") (class "Default")
      (node (ref "U$3") (pin "4") (pinfunction "4.SHDN_4") (pintype "bidirectional"))
    )
    (net (code "74") (name "unconnected-(U$7-1.RTS-Pad1)") (class "Default")
      (node (ref "U$7") (pin "1") (pinfunction "1.RTS_1") (pintype "bidirectional"))
    )
    (net (code "75") (name "unconnected-(U$7-4.5V-Pad4)") (class "Default")
      (node (ref "U$7") (pin "4") (pinfunction "4.5V_4") (pintype "bidirectional"))
    )
    (net (code "76") (name "unconnected-(U$7-5.CTS-Pad5)") (class "Default")
      (node (ref "U$7") (pin "5") (pinfunction "5.CTS_5") (pintype "bidirectional"))
    )
    (net (code "77") (name "unconnected-(U$8-7.BL-Pad7)") (class "Default")
      (node (ref "U$8") (pin "7") (pinfunction "7.BL_7") (pintype "bidirectional"))
    )
    (net (code "78") (name "unconnected-(U$9-11.NC-Pad11)") (class "Default")
      (node (ref "U$9") (pin "11") (pinfunction "11.NC_11") (pintype "bidirectional"))
    )
    (net (code "79") (name "unconnected-(U$9-14.NC-Pad14)") (class "Default")
      (node (ref "U$9") (pin "14") (pinfunction "14.NC_14") (pintype "bidirectional"))
    )
    (net (code "80") (name "unconnected-(U$9-19.INTB-Pad19)") (class "Default")
      (node (ref "U$9") (pin "19") (pinfunction "19.INTB_19") (pintype "bidirectional"))
    )
    (net (code "81") (name "unconnected-(U$9-20.INTA-Pad20)") (class "Default")
      (node (ref "U$9") (pin "20") (pinfunction "20.INTA_20") (pintype "bidirectional"))
    )
    (net (code "82") (name "unconnected-(U$11-7.VM-Pad7)") (class "Default")
      (node (ref "U$11") (pin "7") (pinfunction "7.VM_7") (pintype "bidirectional"))
    )
  )
)
